# Shield_IPS_Color_Display.net
KiCad netlist of a schematic drawn in EAGLE
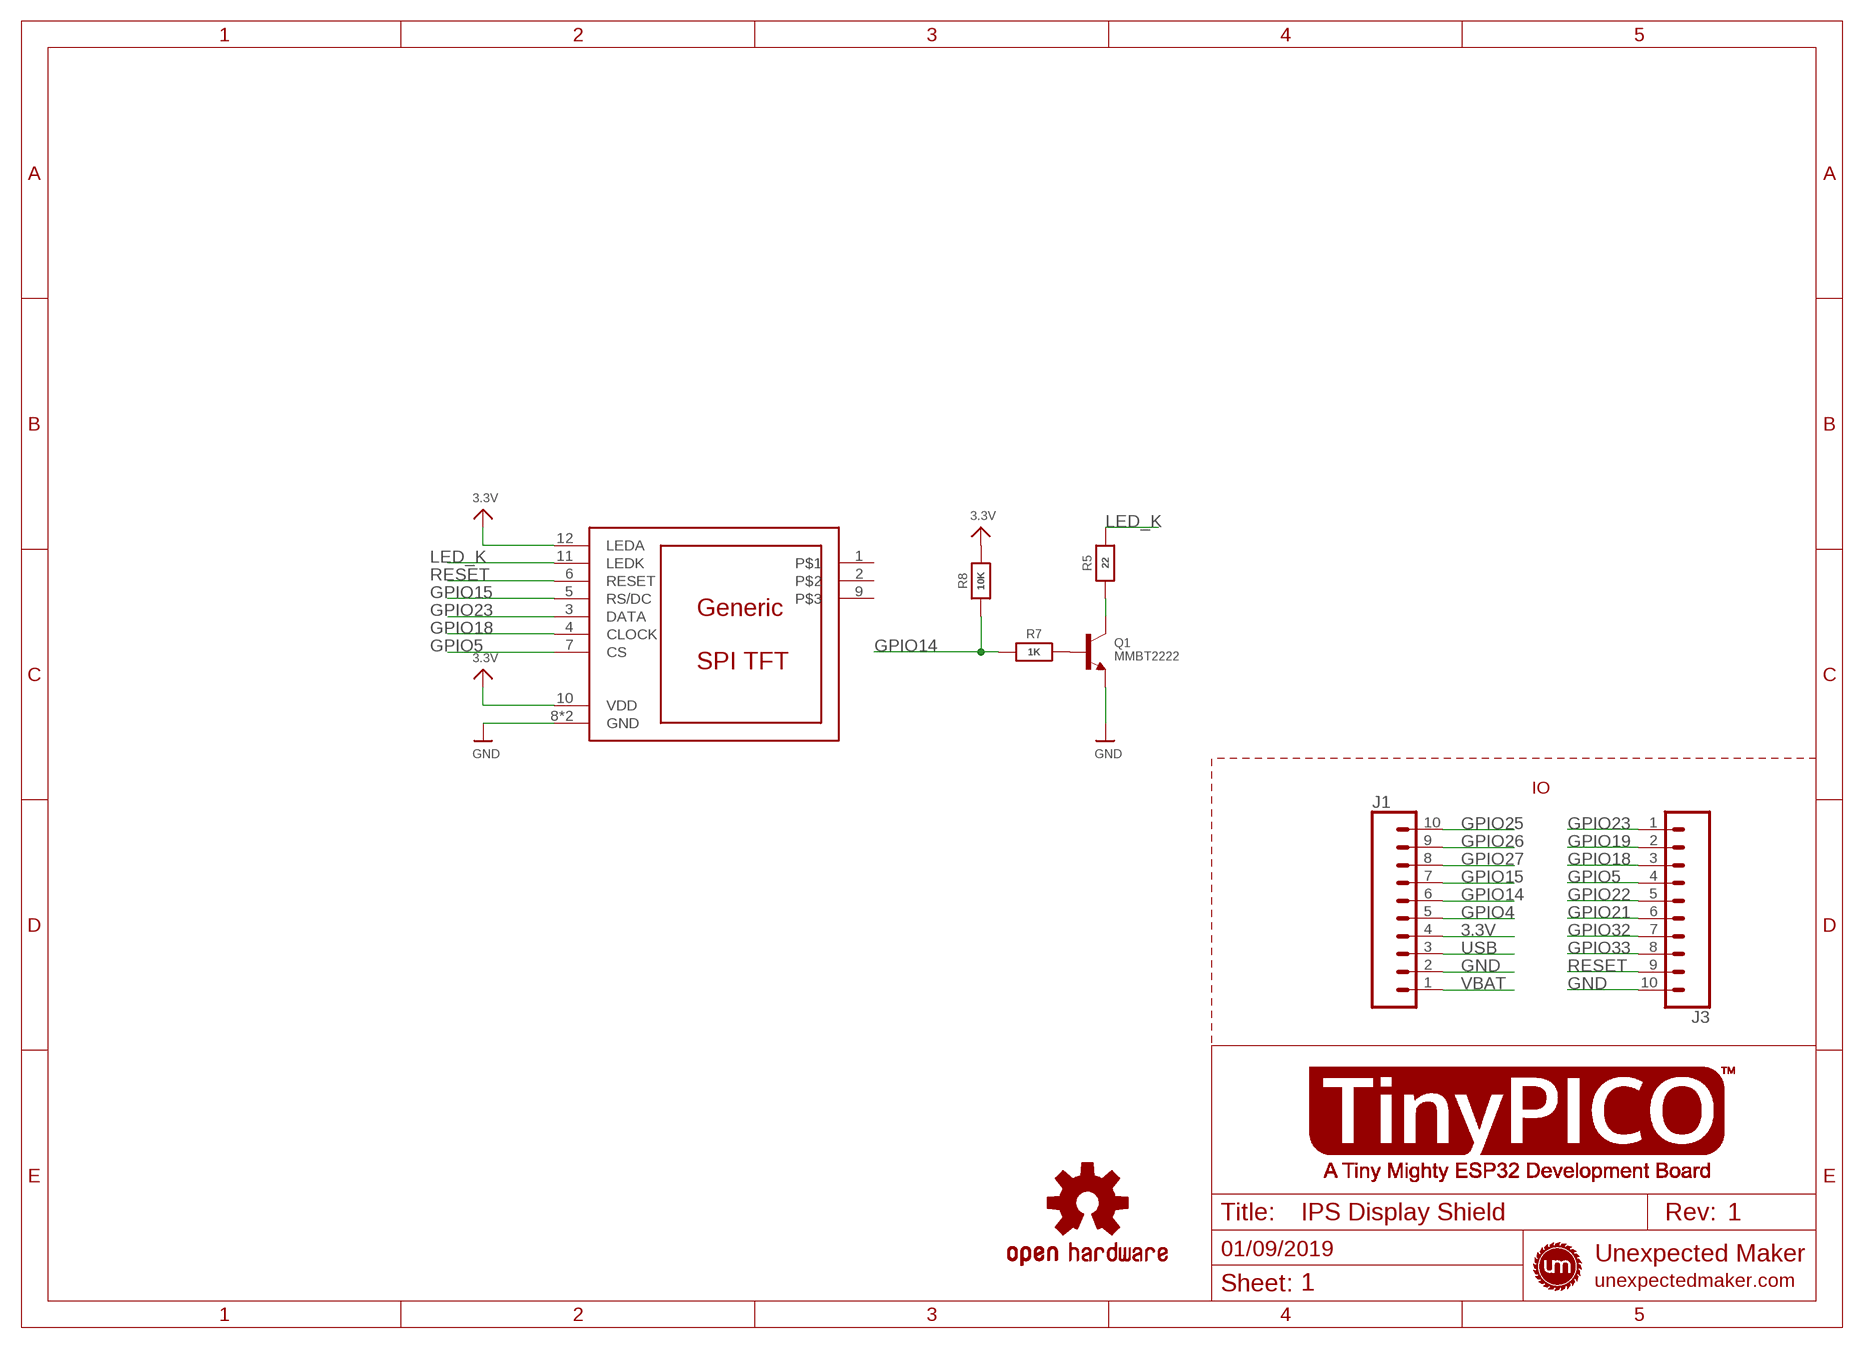
[diagram p0: schematic, sheet 1]

(export (version "E")
  (design (tool "Eeschema 10.0.6"))
  (components
    (comp (ref "J1")
      (value "TINYPICO_HEADER_10SQR")
      (footprint "eagle-import:1X10_NO_SILK_SQR")
      (libsource (lib "eagle-import") (part "TINYPICO_HEADER_10SQR"))
    )
    (comp (ref "J3")
      (value "TINYPICO_HEADER_10SQR")
      (footprint "eagle-import:1X10_NO_SILK_SQR")
      (libsource (lib "eagle-import") (part "TINYPICO_HEADER_10SQR"))
    )
    (comp (ref "LOGO1")
      (value "OSHW-LOGOS")
      (footprint "eagle-import:OSHW-LOGO-S")
      (libsource (lib "eagle-import") (part "OSHW-LOGOS"))
    )
    (comp (ref "Q1")
      (value "MMBT2222")
      (footprint "eagle-import:SOT23-WIDE")
      (libsource (lib "eagle-import") (part "TRANSISTOR_NPNWIDE"))
    )
    (comp (ref "R5")
      (value "22")
      (footprint "eagle-import:_0603MP")
      (libsource (lib "eagle-import") (part "RESISTOR_0603MP"))
    )
    (comp (ref "R7")
      (value "1K")
      (footprint "eagle-import:_0603MP")
      (libsource (lib "eagle-import") (part "RESISTOR_0603MP"))
    )
    (comp (ref "R8")
      (value "10K")
      (footprint "eagle-import:_0603MP")
      (libsource (lib "eagle-import") (part "RESISTOR_0603MP"))
    )
    (comp (ref "U$2")
      (value "MICROBUILDER_DISP_LCD_0.9IN_160X80")
      (footprint "eagle-import:MICROBUILDER_TFT_0.96IN_160X80")
      (libsource (lib "eagle-import") (part "MICROBUILDER_DISP_LCD_0.9IN_160X80"))
    )
  )
  (nets
    (net (code "1") (name "/GPIO4") (class "Default")
      (node (ref "J1") (pin "5") (pinfunction "5_5") (pintype "passive"))
    )
    (net (code "2") (name "/GPIO5") (class "Default")
      (node (ref "J3") (pin "4") (pinfunction "4_4") (pintype "passive"))
      (node (ref "U$2") (pin "7") (pinfunction "CS_7") (pintype "input"))
    )
    (net (code "3") (name "/GPIO14") (class "Default")
      (node (ref "J1") (pin "6") (pinfunction "6_6") (pintype "passive"))
      (node (ref "R7") (pin "1") (pinfunction "1_1") (pintype "passive"))
      (node (ref "R8") (pin "1") (pinfunction "1_1") (pintype "passive"))
    )
    (net (code "4") (name "/GPIO15") (class "Default")
      (node (ref "J1") (pin "7") (pinfunction "7_7") (pintype "passive"))
      (node (ref "U$2") (pin "5") (pinfunction "RS/DC_5") (pintype "input"))
    )
    (net (code "5") (name "/GPIO18") (class "Default")
      (node (ref "J3") (pin "3") (pinfunction "3_3") (pintype "passive"))
      (node (ref "U$2") (pin "4") (pinfunction "CLOCK_4") (pintype "input"))
    )
    (net (code "6") (name "/GPIO19") (class "Default")
      (node (ref "J3") (pin "2") (pinfunction "2_2") (pintype "passive"))
    )
    (net (code "7") (name "/GPIO21") (class "Default")
      (node (ref "J3") (pin "6") (pinfunction "6_6") (pintype "passive"))
    )
    (net (code "8") (name "/GPIO22") (class "Default")
      (node (ref "J3") (pin "5") (pinfunction "5_5") (pintype "passive"))
    )
    (net (code "9") (name "/GPIO23") (class "Default")
      (node (ref "J3") (pin "1") (pinfunction "1_1") (pintype "passive"))
      (node (ref "U$2") (pin "3") (pinfunction "DATA_3") (pintype "bidirectional"))
    )
    (net (code "10") (name "/GPIO25") (class "Default")
      (node (ref "J1") (pin "10") (pinfunction "10_10") (pintype "passive"))
    )
    (net (code "11") (name "/GPIO26") (class "Default")
      (node (ref "J1") (pin "9") (pinfunction "9_9") (pintype "passive"))
    )
    (net (code "12") (name "/GPIO27") (class "Default")
      (node (ref "J1") (pin "8") (pinfunction "8_8") (pintype "passive"))
    )
    (net (code "13") (name "/GPIO32") (class "Default")
      (node (ref "J3") (pin "7") (pinfunction "7_7") (pintype "passive"))
    )
    (net (code "14") (name "/GPIO33") (class "Default")
      (node (ref "J3") (pin "8") (pinfunction "8_8") (pintype "passive"))
    )
    (net (code "15") (name "/LED_K") (class "Default")
      (node (ref "R5") (pin "2") (pinfunction "2_2") (pintype "passive"))
      (node (ref "U$2") (pin "11") (pinfunction "LEDK_11") (pintype "input"))
    )
    (net (code "16") (name "/RESET") (class "Default")
      (node (ref "J3") (pin "9") (pinfunction "9_9") (pintype "passive"))
      (node (ref "U$2") (pin "6") (pinfunction "RESET_6") (pintype "input"))
    )
    (net (code "17") (name "/USB") (class "Default")
      (node (ref "J1") (pin "3") (pinfunction "3_3") (pintype "passive"))
    )
    (net (code "18") (name "/VBAT") (class "Default")
      (node (ref "J1") (pin "1") (pinfunction "1_1") (pintype "passive"))
    )
    (net (code "19") (name "3.3V") (class "Default")
      (node (ref "J1") (pin "4") (pinfunction "4_4") (pintype "passive"))
      (node (ref "R8") (pin "2") (pinfunction "2_2") (pintype "passive"))
      (node (ref "U$2") (pin "10") (pinfunction "VDD_10") (pintype "power_in"))
      (node (ref "U$2") (pin "12") (pinfunction "LEDA_12") (pintype "input"))
    )
    (net (code "20") (name "GND") (class "Default")
      (node (ref "J1") (pin "2") (pinfunction "2_2") (pintype "passive"))
      (node (ref "J3") (pin "10") (pinfunction "10_10") (pintype "passive"))
      (node (ref "Q1") (pin "2") (pinfunction "E_2") (pintype "passive"))
      (node (ref "U$2") (pin "13") (pinfunction "GND_13") (pintype "power_in"))
      (node (ref "U$2") (pin "8") (pinfunction "GND_8") (pintype "power_in"))
    )
    (net (code "21") (name "Net-(Q1-B)") (class "Default")
      (node (ref "Q1") (pin "1") (pinfunction "B_1") (pintype "passive"))
      (node (ref "R7") (pin "2") (pinfunction "2_2") (pintype "passive"))
    )
    (net (code "22") (name "Net-(Q1-C)") (class "Default")
      (node (ref "Q1") (pin "3") (pinfunction "C_3") (pintype "passive"))
      (node (ref "R5") (pin "1") (pinfunction "1_1") (pintype "passive"))
    )
    (net (code "23") (name "unconnected-(U$2-P$1-Pad1)") (class "Default")
      (node (ref "U$2") (pin "1") (pinfunction "P$1_1") (pintype "no_connect"))
    )
    (net (code "24") (name "unconnected-(U$2-P$2-Pad2)") (class "Default")
      (node (ref "U$2") (pin "2") (pinfunction "P$2_2") (pintype "no_connect"))
    )
    (net (code "25") (name "unconnected-(U$2-P$3-Pad9)") (class "Default")
      (node (ref "U$2") (pin "9") (pinfunction "P$3_9") (pintype "no_connect"))
    )
  )
)
